# Information.net
KiCad netlist of a schematic drawn in Altium Designer
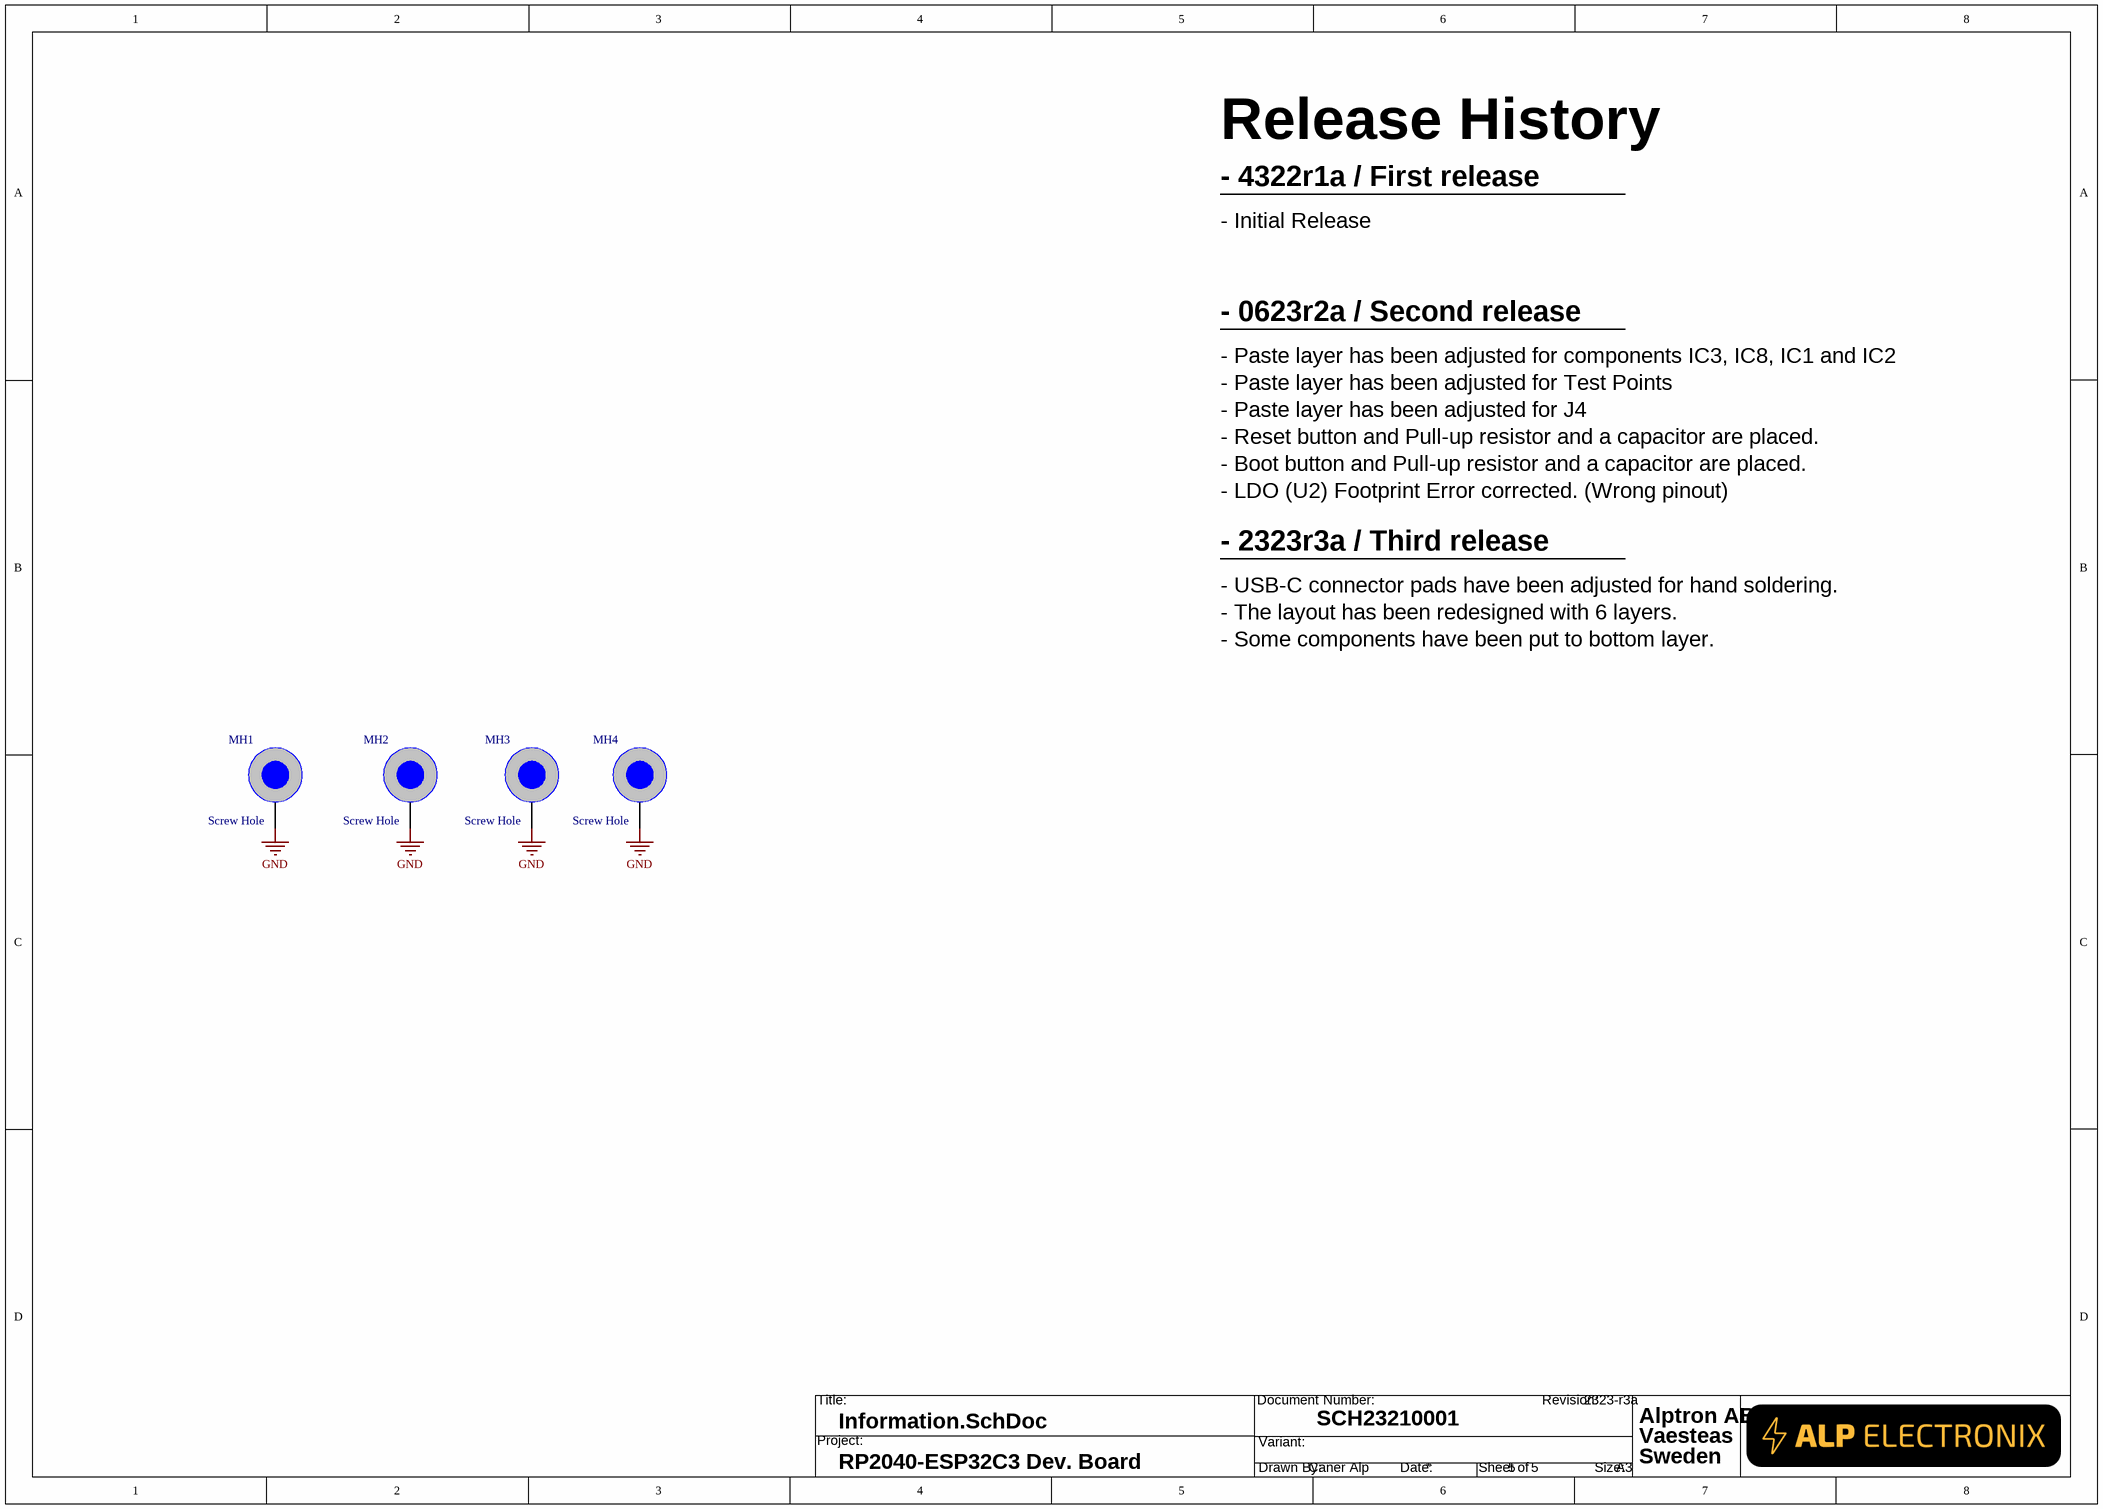
[diagram p0: Information.SchDoc]

(export (version "E")
  (design (tool "Eeschema 10.0.6"))
  (components
    (comp (ref "MH1")
      (value "Screw Hole")
      (footprint "RP2040_ESP32-C3 Dev Board PCB Lib:M3 Screw")
      (libsource (lib "Altium Component") (part "Screw Hole"))
    )
    (comp (ref "MH2")
      (value "Screw Hole")
      (footprint "RP2040_ESP32-C3 Dev Board PCB Lib:M3 Screw")
      (libsource (lib "Altium Component") (part "Screw Hole"))
    )
    (comp (ref "MH3")
      (value "Screw Hole")
      (footprint "RP2040_ESP32-C3 Dev Board PCB Lib:M3 Screw")
      (libsource (lib "Altium Component") (part "Screw Hole"))
    )
    (comp (ref "MH4")
      (value "Screw Hole")
      (footprint "RP2040_ESP32-C3 Dev Board PCB Lib:M3 Screw")
      (libsource (lib "Altium Component") (part "Screw Hole"))
    )
  )
  (nets
    (net (code "1") (name "GND") (class "Default")
      (node (ref "MH1") (pin "1") (pinfunction "1_1") (pintype "passive"))
      (node (ref "MH2") (pin "1") (pinfunction "1_1") (pintype "passive"))
      (node (ref "MH3") (pin "1") (pinfunction "1_1") (pintype "passive"))
      (node (ref "MH4") (pin "1") (pinfunction "1_1") (pintype "passive"))
    )
  )
)
